# DC-DC_TPS65133.net
KiCad netlist of a schematic drawn in Altium Designer
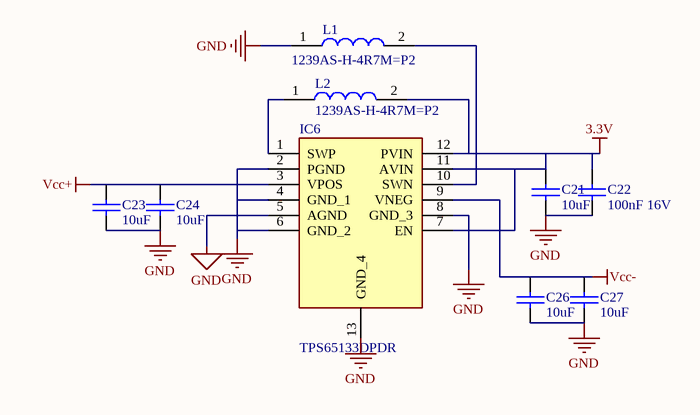
[diagram p0: DC-DC TPS65133.schdoc]

(export (version "E")
  (design (tool "Eeschema 10.0.6"))
  (components
    (comp (ref "C21") (value "10uF") (footprint "0603C") (libsource (lib "电容") (part "CAP-NP")))
    (comp (ref "C22")
      (value "100nF 16V")
      (footprint "0402C")
      (fields (field (name "TOLERANCE") "10%") (field (name "VOLTAGE") "16V"))
      (libsource (lib "电容") (part "CAP-NP"))
    )
    (comp (ref "C23") (value "10uF") (footprint "0603C") (libsource (lib "电容") (part "CAP-NP")))
    (comp (ref "C24") (value "10uF") (footprint "0603C") (libsource (lib "电容") (part "CAP-NP")))
    (comp (ref "C26") (value "10uF") (footprint "0603C") (libsource (lib "电容") (part "CAP-NP")))
    (comp (ref "C27") (value "10uF") (footprint "0603C") (libsource (lib "电容") (part "CAP-NP")))
    (comp (ref "IC6")
      (value "TPS65133DPDR")
      (footprint "SamacSys:SON45P300X300X80-13N-D")
      (description "Integrated Circuit")
      (fields (field (name "MOUSER PART NUMBER") "595-TPS65133DPDR"))
      (libsource (lib "*") (part "TPS65133DPDR"))
    )
    (comp (ref "L1")
      (value "1239AS-H-4R7M=P2")
      (footprint "SamacSys:DFE2HCAH1R0MJ0L")
      (description "Inductor")
      (fields (field (name "MOUSER PART NUMBER") "81-1239AS-H-4R7MP2"))
      (libsource (lib "*") (part "1239AS-H-4R7M=P2"))
    )
    (comp (ref "L2")
      (value "1239AS-H-4R7M=P2")
      (footprint "SamacSys:DFE2HCAH1R0MJ0L")
      (description "Inductor")
      (fields (field (name "MOUSER PART NUMBER") "81-1239AS-H-4R7MP2"))
      (libsource (lib "*") (part "1239AS-H-4R7M=P2"))
    )
  )
  (nets
    (net (code "1") (name "3.3V") (class "Default")
      (node (ref "C21") (pin "1") (pinfunction "1_1") (pintype "passive"))
      (node (ref "C22") (pin "2") (pinfunction "2_2") (pintype "passive"))
      (node (ref "IC6") (pin "11") (pinfunction "AVIN_11") (pintype "passive"))
      (node (ref "IC6") (pin "12") (pinfunction "PVIN_12") (pintype "passive"))
      (node (ref "IC6") (pin "7") (pinfunction "EN_7") (pintype "passive"))
      (node (ref "L2") (pin "2") (pinfunction "2_2") (pintype "passive"))
    )
    (net (code "2") (name "GND") (class "Default")
      (node (ref "C21") (pin "2") (pinfunction "2_2") (pintype "passive"))
      (node (ref "C22") (pin "1") (pinfunction "1_1") (pintype "passive"))
      (node (ref "C23") (pin "2") (pinfunction "2_2") (pintype "passive"))
      (node (ref "C24") (pin "2") (pinfunction "2_2") (pintype "passive"))
      (node (ref "C26") (pin "2") (pinfunction "2_2") (pintype "passive"))
      (node (ref "C27") (pin "2") (pinfunction "2_2") (pintype "passive"))
      (node (ref "IC6") (pin "13") (pinfunction "GND_4_13") (pintype "passive"))
      (node (ref "IC6") (pin "2") (pinfunction "PGND_2") (pintype "passive"))
      (node (ref "IC6") (pin "4") (pinfunction "GND_1_4") (pintype "passive"))
      (node (ref "IC6") (pin "5") (pinfunction "AGND_5") (pintype "passive"))
      (node (ref "IC6") (pin "6") (pinfunction "GND_2_6") (pintype "passive"))
      (node (ref "IC6") (pin "8") (pinfunction "GND_3_8") (pintype "passive"))
      (node (ref "L1") (pin "1") (pinfunction "1_1") (pintype "passive"))
    )
    (net (code "3") (name "Net-(IC6-SWN)") (class "Default")
      (node (ref "IC6") (pin "10") (pinfunction "SWN_10") (pintype "passive"))
      (node (ref "L1") (pin "2") (pinfunction "2_2") (pintype "passive"))
    )
    (net (code "4") (name "Net-(IC6-SWP)") (class "Default")
      (node (ref "IC6") (pin "1") (pinfunction "SWP_1") (pintype "passive"))
      (node (ref "L2") (pin "1") (pinfunction "1_1") (pintype "passive"))
    )
    (net (code "5") (name "Vcc+") (class "Default")
      (node (ref "C23") (pin "1") (pinfunction "1_1") (pintype "passive"))
      (node (ref "C24") (pin "1") (pinfunction "1_1") (pintype "passive"))
      (node (ref "IC6") (pin "3") (pinfunction "VPOS_3") (pintype "passive"))
    )
    (net (code "6") (name "Vcc-") (class "Default")
      (node (ref "C26") (pin "1") (pinfunction "1_1") (pintype "passive"))
      (node (ref "C27") (pin "1") (pinfunction "1_1") (pintype "passive"))
      (node (ref "IC6") (pin "9") (pinfunction "VNEG_9") (pintype "passive"))
    )
  )
)
